# Sheet1.net
KiCad netlist of a schematic drawn in Altium Designer
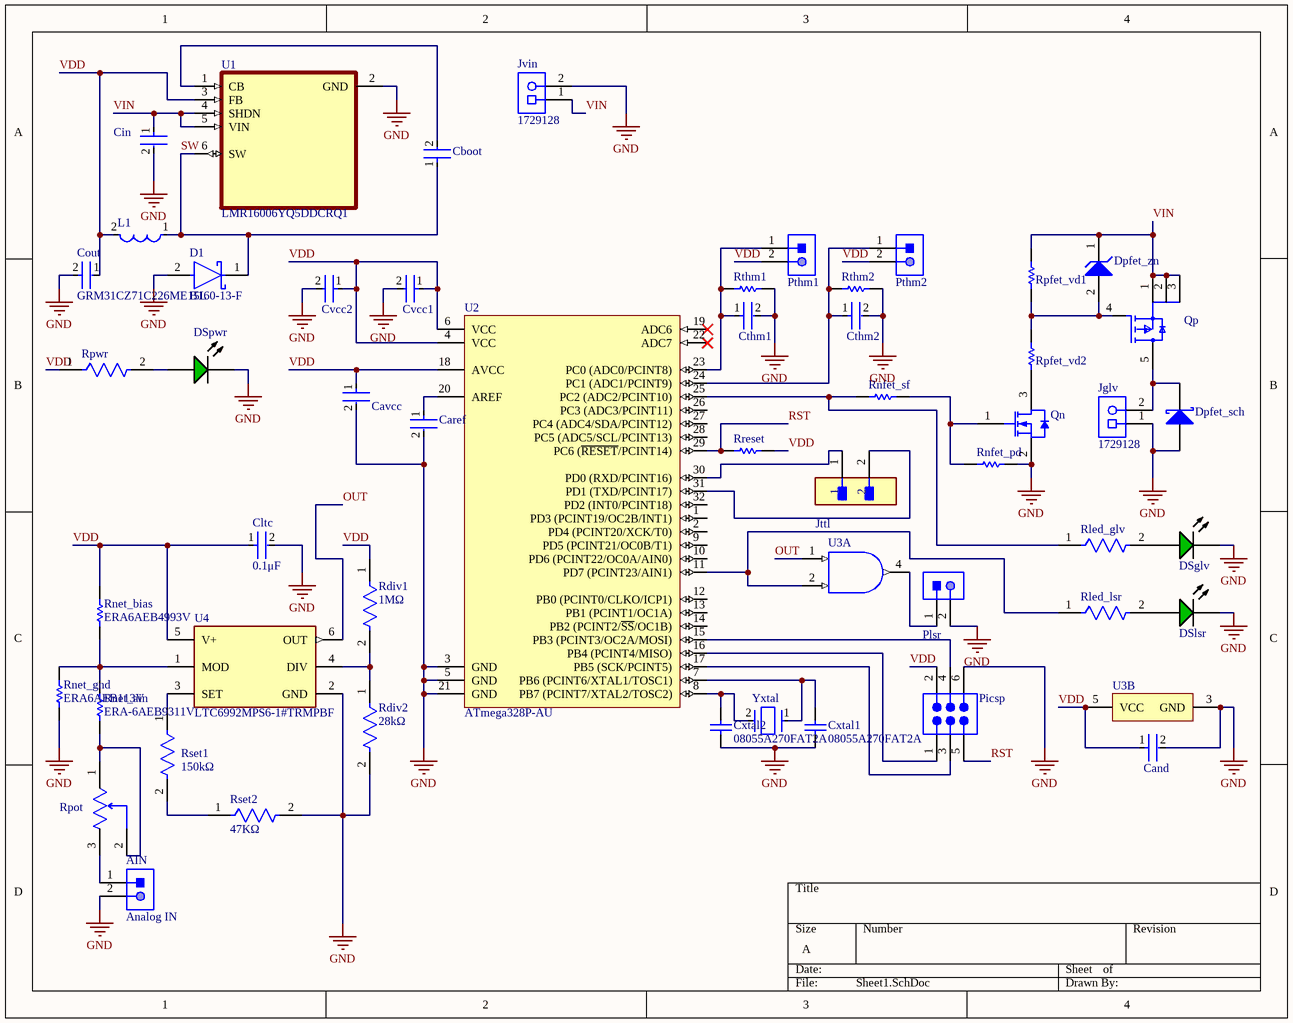
[diagram p0: Sheet1.SchDoc]

(export (version "E")
  (design (tool "Eeschema 10.0.6"))
  (components
    (comp (ref "AIN")
      (value "Analog IN")
      (footprint "JST-S2B-XH-A(LF)(SN)_V")
      (fields (field (name "TOLERANCE") "10%"))
      (libsource (lib "") (part "CN-1P-M-R2_1"))
    )
    (comp (ref "Cand")
      (value "GCM21BR72A104KA37L")
      (footprint "FP-GCM21B-0_15-MFG")
      (description "Ceramic Capacitor for Automotive 100nF ±10% 100VDC X7R 0805 Embossed T/R")
      (fields (field (name "TOLERANCE") "10%") (field (name "VOLTAGE") "100V"))
      (libsource (lib "Altium Content Vault") (part "02cd4be3c70576c341d710602a673aa"))
    )
    (comp (ref "Caref")
      (value "GCM21BR72A104KA37L")
      (footprint "FP-GCM21B-0_15-MFG")
      (description "Ceramic Capacitor for Automotive 100nF ±10% 100VDC X7R 0805 Embossed T/R")
      (fields (field (name "TOLERANCE") "10%") (field (name "VOLTAGE") "100V"))
      (libsource (lib "Altium Content Vault") (part "02cd4be3c70576c341d710602a673aa"))
    )
    (comp (ref "Cavcc")
      (value "GCM21BR72A104KA37L")
      (footprint "FP-GCM21B-0_15-MFG")
      (description "Ceramic Capacitor for Automotive 100nF ±10% 100VDC X7R 0805 Embossed T/R")
      (fields (field (name "TOLERANCE") "10%") (field (name "VOLTAGE") "100V"))
      (libsource (lib "Altium Content Vault") (part "02cd4be3c70576c341d710602a673aa"))
    )
    (comp (ref "Cboot")
      (value "GRM21BR71H474KA88L")
      (footprint "FP-GRM21B-0_1-IPC_B")
      (description "Chip Multilayer Ceramic Capacitors for General Purpose, 0805, 0.47uF, X7R, 15%, 10%, 50V")
      (fields (field (name "VOLTAGE") "50V") (field (name "TOLERANCE") "10%"))
      (libsource (lib "Altium Content Vault") (part "b4654b650e69147ec39a6b967a45e02"))
    )
    (comp (ref "Cin")
      (value "GRM31CR71H475KA12L")
      (footprint "FP-GRM31C-0_2-e0_3_0_8-IPC_C")
      (description "Chip Multilayer Ceramic Capacitors for General Purpose, 1206, 4.7uF, X7R, 15%, 10%, 50V")
      (fields (field (name "VOLTAGE") "50V") (field (name "TOLERANCE") "10%"))
      (libsource (lib "Altium Content Vault") (part "02cd4be3c70576c341d710602a673aa"))
    )
    (comp (ref "Cltc")
      (value "0.1μF")
      (footprint "FP-GCM21B-0_15-MFG")
      (description "Ceramic Capacitor for Automotive 100nF ±10% 100VDC X7R 0805 Embossed T/R")
      (fields (field (name "TOLERANCE") "10%") (field (name "VOLTAGE") "100V"))
      (libsource (lib "Altium Content Vault") (part "02cd4be3c70576c341d710602a673aa"))
    )
    (comp (ref "Cout")
      (value "GRM31CZ71C226ME15L")
      (footprint "FP-GRM31C-0_3-e0_3_0_8-IPC_C")
      (description "Chip Multilayer Ceramic Capacitors for General Purpose, 1206, 22uF, X7R, 15%, 20%, 16V")
      (libsource (lib "Altium Content Vault") (part "f23184f103b6ebe33a8c269c53dcba6"))
    )
    (comp (ref "Cthm1")
      (value "GCM21BR72A104KA37L")
      (footprint "FP-GCM21B-0_15-MFG")
      (description "Ceramic Capacitor for Automotive 100nF ±10% 100VDC X7R 0805 Embossed T/R")
      (fields (field (name "TOLERANCE") "10%") (field (name "VOLTAGE") "100V"))
      (libsource (lib "Altium Content Vault") (part "02cd4be3c70576c341d710602a673aa"))
    )
    (comp (ref "Cthm2")
      (value "GCM21BR72A104KA37L")
      (footprint "FP-GCM21B-0_15-MFG")
      (description "Ceramic Capacitor for Automotive 100nF ±10% 100VDC X7R 0805 Embossed T/R")
      (fields (field (name "TOLERANCE") "10%") (field (name "VOLTAGE") "100V"))
      (libsource (lib "Altium Content Vault") (part "02cd4be3c70576c341d710602a673aa"))
    )
    (comp (ref "Cvcc1")
      (value "GCM21BR72A104KA37L")
      (footprint "FP-GCM21B-0_15-MFG")
      (description "Ceramic Capacitor for Automotive 100nF ±10% 100VDC X7R 0805 Embossed T/R")
      (fields (field (name "TOLERANCE") "10%") (field (name "VOLTAGE") "100V"))
      (libsource (lib "Altium Content Vault") (part "02cd4be3c70576c341d710602a673aa"))
    )
    (comp (ref "Cvcc2")
      (value "GCM21BR72A104KA37L")
      (footprint "FP-GCM21B-0_15-MFG")
      (description "Ceramic Capacitor for Automotive 100nF ±10% 100VDC X7R 0805 Embossed T/R")
      (fields (field (name "TOLERANCE") "10%") (field (name "VOLTAGE") "100V"))
      (libsource (lib "Altium Content Vault") (part "02cd4be3c70576c341d710602a673aa"))
    )
    (comp (ref "Cxtal1")
      (value "08055A270FAT2A")
      (footprint "CAPC2013X94X50NL20T25")
      (fields (field (name "MANUFACTURER") "AVX Interconnect / Elco"))
      (libsource (lib "Altium Content Vault") (part "CAP"))
    )
    (comp (ref "Cxtal2")
      (value "08055A270FAT2A")
      (footprint "CAPC2013X94X50NL20T25")
      (fields (field (name "MANUFACTURER") "AVX Interconnect / Elco"))
      (libsource (lib "Altium Content Vault") (part "CAP"))
    )
    (comp (ref "D1")
      (value "B160-13-F")
      (footprint "FP-SMA-MFG")
      (description "DIODE SCHOTTKY 60V 1A SMA")
      (libsource (lib "Altium Content Vault") (part "1d6ec82d83fb6aee721767c19dac4b9"))
    )
    (comp (ref "Dpfet_sch")
      (value "B560C-13-F")
      (footprint "DIOD-B5X0C-2_M")
      (description "Schottky Barrier Rectifier, 5 A, 60 V, -55 to 125 degC, 2-Pin SMD, RoHS, Tape and Reel")
      (fields (field (name "MANUFACTURER") "DiodesIncorporated"))
      (libsource (lib "Altium Content Vault") (part "DSKY-KA-2"))
    )
    (comp (ref "Dpfet_zn")
      (value "MMSZ5245BT1G")
      (footprint "ONSC-SOD-123-2-425-04_V")
      (description "Zener Voltage Regulator, 500 mW, 2-Pin SOD-123, Pb-Free, Tape and Reel")
      (fields (field (name "MANUFACTURER") "On Semiconductor"))
      (libsource (lib "Altium Content Vault") (part "ONSC-K1A2-2"))
    )
    (comp (ref "DSglv")
      (value "HSMG-C170")
      (footprint "AVAG-HSMX-C170_V")
      (description "Chip LED, Green, 2.2 V, -40 to 85 degC, 2-Pin SMD, Pb-Free, Tape and Reel")
      (fields (field (name "MANUFACTURER") "Avago"))
      (libsource (lib "Altium Content Vault") (part "LED_GREEN_A1K2-2"))
    )
    (comp (ref "DSlsr")
      (value "HSMG-C170")
      (footprint "AVAG-HSMX-C170_V")
      (description "Chip LED, Green, 2.2 V, -40 to 85 degC, 2-Pin SMD, Pb-Free, Tape and Reel")
      (fields (field (name "MANUFACTURER") "Avago"))
      (libsource (lib "Altium Content Vault") (part "LED_GREEN_A1K2-2"))
    )
    (comp (ref "DSpwr")
      (value "HSMG-C170")
      (footprint "AVAG-HSMX-C170_V")
      (description "Chip LED, Green, 2.2 V, -40 to 85 degC, 2-Pin SMD, Pb-Free, Tape and Reel")
      (fields (field (name "MANUFACTURER") "Avago"))
      (libsource (lib "Altium Content Vault") (part "LED_GREEN_A1K2-2"))
    )
    (comp (ref "Jglv")
      (value "1729128")
      (footprint "PHOE-1729128-2_V")
      (description "PCB Terminal Block, 13.5 A, 400 V, 2-Pin THD, RoHS, Bulk")
      (fields (field (name "MANUFACTURER") "Phoenix Contact"))
      (libsource (lib "Altium Content Vault") (part "CN-2P-F-R2"))
    )
    (comp (ref "Jttl")
      (value "TSW-102-07-F-S")
      (footprint "FP-TSW-102-07-F-S-MFG")
      (description "CONN HEADER VERT 2POS 2.54MM")
      (libsource (lib "Altium Content Vault") (part "3bc925449376181038e59eaffc5286c"))
    )
    (comp (ref "Jvin")
      (value "1729128")
      (footprint "PHOE-1729128-2_V")
      (description "PCB Terminal Block, 13.5 A, 400 V, 2-Pin THD, RoHS, Bulk")
      (fields (field (name "MANUFACTURER") "Phoenix Contact"))
      (libsource (lib "Altium Content Vault") (part "CN-2P-F-R2"))
    )
    (comp (ref "L1")
      (value "LQH5BPN100MT0L")
      (footprint "FP-LQH5BPB_T0-MFG")
      (description "Wire Wound Ferrite Inductor for Power Lines 10μH ±20% 0.1272Ω 1.60A 2020")
      (fields (field (name "TOLERANCE") "20%"))
      (libsource (lib "Altium Content Vault") (part "725321dda6339637d4d059423bc1c3c"))
    )
    (comp (ref "Picsp")
      (value "MTSW-103-07-F-D-244")
      (footprint "SMTC-MTSW-103-07-X-D-244")
      (fields (field (name "MANUFACTURER") "Samtec"))
      (libsource (lib "Altium Content Vault") (part "SMTC-MTSW-103-07-X-D-244"))
    )
    (comp (ref "Plsr")
      (value "S2B-XH-A(LF)(SN)")
      (footprint "JST-S2B-XH-A(LF)(SN)_V")
      (fields (field (name "TOLERANCE") "10%"))
      (libsource (lib "Altium Content Vault") (part "CN-1P-M-R2"))
    )
    (comp (ref "Pthm1")
      (value "S2B-XH-A(LF)(SN)")
      (footprint "JST-S2B-XH-A(LF)(SN)_V")
      (fields (field (name "TOLERANCE") "10%"))
      (libsource (lib "") (part "CN-1P-M-R2_1"))
    )
    (comp (ref "Pthm2")
      (value "S2B-XH-A(LF)(SN)")
      (footprint "JST-S2B-XH-A(LF)(SN)_V")
      (fields (field (name "TOLERANCE") "10%"))
      (libsource (lib "") (part "CN-1P-M-R2_1"))
    )
    (comp (ref "Qn")
      (value "2N7002LT1G")
      (footprint "ONSC-SOT-23-3-318-08_V")
      (description "Small Signal MOSFET, 60 V, 115 mA, N-Channel, 3-Pin SOT-23, Pb-Free, Tape and Reel")
      (fields (field (name "MANUFACTURER") "On Semiconductor"))
      (libsource (lib "Altium Content Vault") (part "ONSC-NMOS-G1S2D3-3"))
    )
    (comp (ref "Qp")
      (value "SQJ459EP-T1_GE3")
      (footprint "FP-C15-1203-SINGLE-MFG")
      (description "MOSFET P-CH 60V 52A POWERPAKSO-8")
      (fields
        (field (name "MANUFACTURER") "Vishay")
        (field (name "OCTOPART") "https://octopart.com/sqj459ep-t1_ge3-vishay-73080141")
      )
      (libsource (lib "Altium Content Vault") (part "5cd5aa5b3d227f8a38aca373915d141"))
    )
    (comp (ref "Rdiv1")
      (value "1MΩ")
      (footprint "FP-RG2012-MFG")
      (description "Automotive Metal Thin Film Chip Resistor, 0805, 1MΩ, 0.1%, 25ppm/°C, 0.125W, 150V")
      (fields (field (name "TOLERANCE") "0.1%"))
      (libsource (lib "Altium Content Vault") (part "1029c3af85768c4190bb7ad29bc67b5"))
    )
    (comp (ref "Rdiv2")
      (value "28kΩ")
      (footprint "FP-RG2012-MFG")
      (description "Automotive Metal Thin Film Chip Resistor, 0805, 280kΩ, 0.1%, 25ppm/°C, 0.125W, 150V")
      (fields (field (name "TOLERANCE") "0.1%"))
      (libsource (lib "Altium Content Vault") (part "1029c3af85768c4190bb7ad29bc67b5"))
    )
    (comp (ref "Rled_glv")
      (value "CRCW08051K20FKEA")
      (footprint "FP-CRCW0805-e3-MFG")
      (description "RES Thick Film, 1.2kΩ, 1%, 0.125W, 100ppm/°C, 0805")
      (fields (field (name "TOLERANCE") "1%"))
      (libsource (lib "Altium Content Vault") (part "1029c3af85768c4190bb7ad29bc67b5"))
    )
    (comp (ref "Rled_lsr")
      (value "CRCW08051K20FKEA")
      (footprint "FP-CRCW0805-e3-MFG")
      (description "RES Thick Film, 1.2kΩ, 1%, 0.125W, 100ppm/°C, 0805")
      (fields (field (name "TOLERANCE") "1%"))
      (libsource (lib "Altium Content Vault") (part "1029c3af85768c4190bb7ad29bc67b5"))
    )
    (comp (ref "Rnet_ain")
      (value "ERA-6AEB9311V")
      (footprint "RESC2013X60X40ML20T25")
      (fields (field (name "PART NUMBER") "ERA6AEB472V") (field (name "MANUFACTURER") "Panasonic"))
      (libsource (lib "Altium Content Vault") (part "RES"))
    )
    (comp (ref "Rnet_bias")
      (value "ERA6AEB4993V")
      (footprint "RESC2013X60X40ML20T25")
      (fields (field (name "MANUFACTURER") "Panasonic"))
      (libsource (lib "Altium Content Vault") (part "RES"))
    )
    (comp (ref "Rnet_gnd")
      (value "ERA6AEB113V")
      (footprint "RESC2013X60X40NL20T25")
      (fields (field (name "MANUFACTURER") "Panasonic"))
      (libsource (lib "Altium Content Vault") (part "RES"))
    )
    (comp (ref "Rnfet_pd")
      (value "ERA-6AEB103V")
      (footprint "RESC2013X60X40LL20T25_A")
      (fields (field (name "TOLERANCE") "0.1%") (field (name "MANUFACTURER") "Panasonic"))
      (libsource (lib "Altium Content Vault") (part "RES-2"))
    )
    (comp (ref "Rnfet_sf")
      (value "ERA6AEB331V")
      (footprint "RESC2013X60X40LL20T25")
      (fields (field (name "MANUFACTURER") "Panasonic"))
      (libsource (lib "Altium Content Vault") (part "RES"))
    )
    (comp (ref "Rpfet_vd1")
      (value "ERA-6AEB103V")
      (footprint "RESC2013X60X40LL20T25_A")
      (fields (field (name "TOLERANCE") "0.1%") (field (name "MANUFACTURER") "Panasonic"))
      (libsource (lib "Altium Content Vault") (part "RES-2"))
    )
    (comp (ref "Rpfet_vd2")
      (value "ERA-6AEB103V")
      (footprint "RESC2013X60X40LL20T25_A")
      (fields (field (name "TOLERANCE") "0.1%") (field (name "MANUFACTURER") "Panasonic"))
      (libsource (lib "Altium Content Vault") (part "RES-2"))
    )
    (comp (ref "Rpot")
      (value "3296W-1-202LF")
      (footprint "FP-3296W-MFG")
      (description "TRIMMER 2K OHM 0.5W PC PIN TOP")
      (fields (field (name "TOLERANCE") "10%"))
      (libsource (lib "Altium Content Vault") (part "81a8d1f2e6c155a1fa928b358d1a42a"))
    )
    (comp (ref "Rpwr")
      (value "CRCW08051K20FKEA")
      (footprint "FP-CRCW0805-e3-MFG")
      (description "RES Thick Film, 1.2kΩ, 1%, 0.125W, 100ppm/°C, 0805")
      (fields (field (name "TOLERANCE") "1%"))
      (libsource (lib "Altium Content Vault") (part "1029c3af85768c4190bb7ad29bc67b5"))
    )
    (comp (ref "Rreset")
      (value "ERA-6AEB103V")
      (footprint "RESC2013X60X40LL20T25_A")
      (fields (field (name "TOLERANCE") "0.1%") (field (name "MANUFACTURER") "Panasonic"))
      (libsource (lib "Altium Content Vault") (part "RES-2"))
    )
    (comp (ref "Rset1")
      (value "150kΩ")
      (footprint "FP-ERA6A-MFG")
      (description "RES 150K OHM 0.1% 1/8W 0805")
      (fields (field (name "TOLERANCE") "0.1%"))
      (libsource (lib "Altium Content Vault") (part "1029c3af85768c4190bb7ad29bc67b5"))
    )
    (comp (ref "Rset2")
      (value "47KΩ")
      (footprint "FP-ERA6A-MFG")
      (fields (field (name "TOLERANCE") "0.1%"))
      (libsource (lib "Altium Content Vault") (part "1029c3af85768c4190bb7ad29bc67b5"))
    )
    (comp (ref "Rthm1")
      (value "ERA-6AEB103V")
      (footprint "RESC2013X60X40LL20T25_A")
      (fields (field (name "TOLERANCE") "0.1%") (field (name "MANUFACTURER") "Panasonic"))
      (libsource (lib "Altium Content Vault") (part "RES-2"))
    )
    (comp (ref "Rthm2")
      (value "ERA-6AEB103V")
      (footprint "RESC2013X60X40LL20T25_A")
      (fields (field (name "TOLERANCE") "0.1%") (field (name "MANUFACTURER") "Panasonic"))
      (libsource (lib "Altium Content Vault") (part "RES-2"))
    )
    (comp (ref "U1")
      (value "LMR16006YQ5DDCRQ1")
      (footprint "SOT95P280X110-6N")
      (description "Automotive Qualified SIMPLE SWITCHER庐 40V (65V transient), 0.6A Buck Regulator with 28渭A IQ")
      (fields (field (name "MF") "Texas Instruments"))
      (libsource (lib "LMR16006YQ5DDCRQ1") (part "LMR16006YQ5DDCRQ1"))
    )
    (comp (ref "U2")
      (value "ATmega328P-AU")
      (footprint "32A_M")
      (libsource (lib "Altium Content Vault") (part "MC-8B-ATM48-SQ32"))
    )
    (comp (ref "U3")
      (value "SN74LVC1G08DBVR")
      (footprint "DBV0005A_M")
      (description "Single 2-Input Positive-AND Gate, DBV0005A, LARGE T&R")
      (fields
        (field (name "GENERIC PART NUMBER") "SN74LVC1G08")
        (field (name "MANUFACTURER") "Texas Instruments")
      )
      (libsource (lib "Altium Content Vault") (part "TI-SN74XXX1X08-5"))
    )
    (comp (ref "U4")
      (value "LTC6992MPS6-1#TRMPBF")
      (footprint "FP-S6-6-05-08-1636-IPC_B")
      (description "IC OSC SILICON PROG TSOT23-6")
      (libsource (lib "Altium Content Vault") (part "8a48498f8010dc692cf6b2ba4f9d0e7"))
    )
    (comp (ref "Yxtal")
      (value "ABLS-16.000MHZ-K4T")
      (footprint "FP-ABLS-MFG")
      (description "CRYSTAL 16.0000MHZ 18PF SMD")
      (fields
        (field (name "TOLERANCE") "30ppm")
        (field (name "OCTOPART") "https://octopart.com/abls-16.000mhz-k4t-abracon-18618626")
      )
      (libsource (lib "Altium Content Vault") (part "c23a69dc6c9e2f18f2079038eb95dd1"))
    )
  )
  (nets
    (net (code "1") (name "/OUT") (class "Default")
      (node (ref "U3") (pin "1") (pinfunction "A_1") (pintype "input"))
      (node (ref "U4") (pin "6") (pinfunction "OUT_6") (pintype "output"))
    )
    (net (code "2") (name "/RST") (class "Default")
      (node (ref "Picsp") (pin "5") (pinfunction "5_5") (pintype "passive"))
      (node (ref "Rreset") (pin "1") (pinfunction "1_1") (pintype "passive"))
      (node (ref "U2") (pin "29") (pinfunction "PC6_(~{RESET}/PCINT14)_29") (pintype "bidirectional"))
    )
    (net (code "3") (name "/SW") (class "Default")
      (node (ref "Cboot") (pin "1") (pinfunction "1_1") (pintype "passive"))
      (node (ref "D1") (pin "1") (pinfunction "C_1") (pintype "passive"))
      (node (ref "L1") (pin "1") (pinfunction "1_1") (pintype "passive"))
      (node (ref "U1") (pin "6") (pinfunction "SW_6") (pintype "bidirectional"))
    )
    (net (code "4") (name "/VDD") (class "Default")
      (node (ref "Cand") (pin "1") (pinfunction "1_1") (pintype "passive"))
      (node (ref "Cavcc") (pin "1") (pinfunction "1_1") (pintype "passive"))
      (node (ref "Cltc") (pin "1") (pinfunction "1_1") (pintype "passive"))
      (node (ref "Cout") (pin "1") (pinfunction "1_1") (pintype "passive"))
      (node (ref "Cvcc1") (pin "1") (pinfunction "1_1") (pintype "passive"))
      (node (ref "Cvcc2") (pin "1") (pinfunction "1_1") (pintype "passive"))
      (node (ref "L1") (pin "2") (pinfunction "2_2") (pintype "passive"))
      (node (ref "Picsp") (pin "2") (pinfunction "2_2") (pintype "passive"))
      (node (ref "Pthm1") (pin "2") (pinfunction "2_2") (pintype "passive"))
      (node (ref "Pthm2") (pin "2") (pinfunction "2_2") (pintype "passive"))
      (node (ref "Rdiv1") (pin "1") (pinfunction "1_1") (pintype "passive"))
      (node (ref "Rnet_bias") (pin "2") (pinfunction "2_2") (pintype "passive"))
      (node (ref "Rpwr") (pin "1") (pinfunction "1_1") (pintype "passive"))
      (node (ref "Rreset") (pin "2") (pinfunction "2_2") (pintype "passive"))
      (node (ref "U1") (pin "3") (pinfunction "FB_3") (pintype "input"))
      (node (ref "U2") (pin "18") (pinfunction "AVCC_18") (pintype "power_in"))
      (node (ref "U2") (pin "4") (pinfunction "VCC_4") (pintype "power_in"))
      (node (ref "U2") (pin "6") (pinfunction "VCC_6") (pintype "power_in"))
      (node (ref "U3") (pin "5") (pinfunction "VCC_5") (pintype "power_in"))
      (node (ref "U4") (pin "5") (pinfunction "V+_5") (pintype "power_in"))
    )
    (net (code "5") (name "/VIN") (class "Default")
      (node (ref "Cin") (pin "1") (pinfunction "1_1") (pintype "passive"))
      (node (ref "Dpfet_zn") (pin "1") (pinfunction "K_1") (pintype "passive"))
      (node (ref "Jvin") (pin "1") (pinfunction "1_1") (pintype "passive"))
      (node (ref "Qp") (pin "1") (pinfunction "S_1") (pintype "passive"))
      (node (ref "Qp") (pin "2") (pinfunction "S_2") (pintype "passive"))
      (node (ref "Qp") (pin "3") (pinfunction "S_3") (pintype "passive"))
      (node (ref "Rpfet_vd1") (pin "2") (pinfunction "2_2") (pintype "passive"))
      (node (ref "U1") (pin "4") (pinfunction "SHDN_4") (pintype "input"))
      (node (ref "U1") (pin "5") (pinfunction "VIN_5") (pintype "input"))
    )
    (net (code "6") (name "GND") (class "Default")
      (node (ref "AIN") (pin "2") (pinfunction "2_2") (pintype "passive"))
      (node (ref "Cand") (pin "2") (pinfunction "2_2") (pintype "passive"))
      (node (ref "Caref") (pin "2") (pinfunction "2_2") (pintype "passive"))
      (node (ref "Cavcc") (pin "2") (pinfunction "2_2") (pintype "passive"))
      (node (ref "Cin") (pin "2") (pinfunction "2_2") (pintype "passive"))
      (node (ref "Cltc") (pin "2") (pinfunction "2_2") (pintype "passive"))
      (node (ref "Cout") (pin "2") (pinfunction "2_2") (pintype "passive"))
      (node (ref "Cthm1") (pin "2") (pinfunction "2_2") (pintype "passive"))
      (node (ref "Cthm2") (pin "2") (pinfunction "2_2") (pintype "passive"))
      (node (ref "Cvcc1") (pin "2") (pinfunction "2_2") (pintype "passive"))
      (node (ref "Cvcc2") (pin "2") (pinfunction "2_2") (pintype "passive"))
      (node (ref "Cxtal1") (pin "1") (pinfunction "1_1") (pintype "passive"))
      (node (ref "Cxtal2") (pin "1") (pinfunction "1_1") (pintype "passive"))
      (node (ref "D1") (pin "2") (pinfunction "A_2") (pintype "passive"))
      (node (ref "DSglv") (pin "2") (pinfunction "K_2") (pintype "passive"))
      (node (ref "DSlsr") (pin "2") (pinfunction "K_2") (pintype "passive"))
      (node (ref "DSpwr") (pin "2") (pinfunction "K_2") (pintype "passive"))
      (node (ref "Dpfet_sch") (pin "2") (pinfunction "A_2") (pintype "passive"))
      (node (ref "Jglv") (pin "1") (pinfunction "1_1") (pintype "passive"))
      (node (ref "Jvin") (pin "2") (pinfunction "2_2") (pintype "passive"))
      (node (ref "Picsp") (pin "6") (pinfunction "6_6") (pintype "passive"))
      (node (ref "Plsr") (pin "2") (pinfunction "2_2") (pintype "passive"))
      (node (ref "Qn") (pin "2") (pinfunction "S_2") (pintype "passive"))
      (node (ref "Rdiv2") (pin "2") (pinfunction "2_2") (pintype "passive"))
      (node (ref "Rnet_gnd") (pin "1") (pinfunction "1_1") (pintype "passive"))
      (node (ref "Rnfet_pd") (pin "2") (pinfunction "2_2") (pintype "passive"))
      (node (ref "Rset2") (pin "2") (pinfunction "2_2") (pintype "passive"))
      (node (ref "Rthm1") (pin "2") (pinfunction "2_2") (pintype "passive"))
      (node (ref "Rthm2") (pin "2") (pinfunction "2_2") (pintype "passive"))
      (node (ref "U1") (pin "2") (pinfunction "GND_2") (pintype "power_in"))
      (node (ref "U2") (pin "21") (pinfunction "GND_21") (pintype "power_in"))
      (node (ref "U2") (pin "3") (pinfunction "GND_3") (pintype "power_in"))
      (node (ref "U2") (pin "5") (pinfunction "GND_5") (pintype "power_in"))
      (node (ref "U3") (pin "3") (pinfunction "GND_3") (pintype "power_in"))
      (node (ref "U4") (pin "2") (pinfunction "GND_2") (pintype "power_in"))
    )
    (net (code "7") (name "Net-(DSglv-A)") (class "Default")
      (node (ref "DSglv") (pin "1") (pinfunction "A_1") (pintype "passive"))
      (node (ref "Rled_glv") (pin "2") (pinfunction "2_2") (pintype "passive"))
    )
    (net (code "8") (name "Net-(DSlsr-A)") (class "Default")
      (node (ref "DSlsr") (pin "1") (pinfunction "A_1") (pintype "passive"))
      (node (ref "Rled_lsr") (pin "2") (pinfunction "2_2") (pintype "passive"))
    )
    (net (code "9") (name "Net-(DSpwr-A)") (class "Default")
      (node (ref "DSpwr") (pin "1") (pinfunction "A_1") (pintype "passive"))
      (node (ref "Rpwr") (pin "2") (pinfunction "2_2") (pintype "passive"))
    )
    (net (code "10") (name "Net-(Dpfet_sch-K)") (class "Default")
      (node (ref "Dpfet_sch") (pin "1") (pinfunction "K_1") (pintype "passive"))
      (node (ref "Jglv") (pin "2") (pinfunction "2_2") (pintype "passive"))
      (node (ref "Qp") (pin "5") (pinfunction "D_5") (pintype "passive"))
    )
    (net (code "11") (name "Net-(Dpfet_zn-A)") (class "Default")
      (node (ref "Dpfet_zn") (pin "2") (pinfunction "A_2") (pintype "passive"))
      (node (ref "Qp") (pin "4") (pinfunction "G_4") (pintype "passive"))
      (node (ref "Rpfet_vd1") (pin "1") (pinfunction "1_1") (pintype "passive"))
      (node (ref "Rpfet_vd2") (pin "1") (pinfunction "1_1") (pintype "passive"))
    )
    (net (code "12") (name "Net-(Qn-D)") (class "Default")
      (node (ref "Qn") (pin "3") (pinfunction "D_3") (pintype "passive"))
      (node (ref "Rpfet_vd2") (pin "2") (pinfunction "2_2") (pintype "passive"))
    )
    (net (code "13") (name "Net-(Qn-G)") (class "Default")
      (node (ref "Qn") (pin "1") (pinfunction "G_1") (pintype "passive"))
      (node (ref "Rnfet_pd") (pin "1") (pinfunction "1_1") (pintype "passive"))
      (node (ref "Rnfet_sf") (pin "2") (pinfunction "2_2") (pintype "passive"))
    )
    (net (code "14") (name "Net-(Rpot-CCW)") (class "Default")
      (node (ref "Rnet_ain") (pin "1") (pinfunction "1_1") (pintype "passive"))
      (node (ref "Rpot") (pin "1") (pinfunction "CCW_1") (pintype "passive"))
      (node (ref "Rpot") (pin "2") (pinfunction "WIPER_2") (pintype "passive"))
    )
    (net (code "15") (name "Net-(Rpot-CW)") (class "Default")
      (node (ref "AIN") (pin "1") (pinfunction "1_1") (pintype "passive"))
      (node (ref "Rpot") (pin "3") (pinfunction "CW_3") (pintype "passive"))
    )
    (net (code "16") (name "Net-(Rset1-Pad2)") (class "Default")
      (node (ref "Rset1") (pin "2") (pinfunction "2_2") (pintype "passive"))
      (node (ref "Rset2") (pin "1") (pinfunction "1_1") (pintype "passive"))
    )
    (net (code "17") (name "Net-(U1-CB)") (class "Default")
      (node (ref "Cboot") (pin "2") (pinfunction "2_2") (pintype "passive"))
      (node (ref "U1") (pin "1") (pinfunction "CB_1") (pintype "input"))
    )
    (net (code "18") (name "Net-(U2-AREF)") (class "Default")
      (node (ref "Caref") (pin "1") (pinfunction "1_1") (pintype "passive"))
      (node (ref "U2") (pin "20") (pinfunction "AREF_20") (pintype "passive"))
    )
    (net (code "19") (name "Net-(U2-PB3_(PCINT3{slash}OC2A{slash}MOSI))") (class "Default")
      (node (ref "Picsp") (pin "4") (pinfunction "4_4") (pintype "passive"))
      (node (ref "U2") (pin "15") (pinfunction "PB3_(PCINT3/OC2A/MOSI)_15") (pintype "bidirectional"))
    )
    (net (code "20") (name "Net-(U2-PB4_(PCINT4{slash}MISO))") (class "Default")
      (node (ref "Picsp") (pin "1") (pinfunction "1_1") (pintype "passive"))
      (node (ref "U2") (pin "16") (pinfunction "PB4_(PCINT4/MISO)_16") (pintype "bidirectional"))
    )
    (net (code "21") (name "Net-(U2-PB5_(SCK{slash}PCINT5))") (class "Default")
      (node (ref "Picsp") (pin "3") (pinfunction "3_3") (pintype "passive"))
      (node (ref "U2") (pin "17") (pinfunction "PB5_(SCK/PCINT5)_17") (pintype "bidirectional"))
    )
    (net (code "22") (name "Net-(U2-PB6_(PCINT6{slash}XTAL1{slash}TOSC1))") (class "Default")
      (node (ref "Cxtal1") (pin "2") (pinfunction "2_2") (pintype "passive"))
      (node (ref "U2") (pin "7") (pinfunction "PB6_(PCINT6/XTAL1/TOSC1)_7") (pintype "bidirectional"))
      (node (ref "Yxtal") (pin "1") (pinfunction "1_1") (pintype "passive"))
    )
    (net (code "23") (name "Net-(U2-PB7_(PCINT7{slash}XTAL2{slash}TOSC2))") (class "Default")
      (node (ref "Cxtal2") (pin "2") (pinfunction "2_2") (pintype "passive"))
      (node (ref "U2") (pin "8") (pinfunction "PB7_(PCINT7/XTAL2/TOSC2)_8") (pintype "bidirectional"))
      (node (ref "Yxtal") (pin "2") (pinfunction "2_2") (pintype "passive"))
    )
    (net (code "24") (name "Net-(U2-PC0_(ADC0{slash}PCINT8))") (class "Default")
      (node (ref "Cthm1") (pin "1") (pinfunction "1_1") (pintype "passive"))
      (node (ref "Pthm1") (pin "1") (pinfunction "1_1") (pintype "passive"))
      (node (ref "Rthm1") (pin "1") (pinfunction "1_1") (pintype "passive"))
      (node (ref "U2") (pin "23") (pinfunction "PC0_(ADC0/PCINT8)_23") (pintype "bidirectional"))
    )
    (net (code "25") (name "Net-(U2-PC1_(ADC1{slash}PCINT9))") (class "Default")
      (node (ref "Cthm2") (pin "1") (pinfunction "1_1") (pintype "passive"))
      (node (ref "Pthm2") (pin "1") (pinfunction "1_1") (pintype "passive"))
      (node (ref "Rthm2") (pin "1") (pinfunction "1_1") (pintype "passive"))
      (node (ref "U2") (pin "24") (pinfunction "PC1_(ADC1/PCINT9)_24") (pintype "bidirectional"))
    )
    (net (code "26") (name "Net-(U2-PC2_(ADC2{slash}PCINT10))") (class "Default")
      (node (ref "Rled_glv") (pin "1") (pinfunction "1_1") (pintype "passive"))
      (node (ref "Rnfet_sf") (pin "1") (pinfunction "1_1") (pintype "passive"))
      (node (ref "U2") (pin "25") (pinfunction "PC2_(ADC2/PCINT10)_25") (pintype "bidirectional"))
    )
    (net (code "27") (name "Net-(U2-PD0_(RXD{slash}PCINT16))") (class "Default")
      (node (ref "Jttl") (pin "1") (pinfunction "1_1") (pintype "passive"))
      (node (ref "U2") (pin "30") (pinfunction "PD0_(RXD/PCINT16)_30") (pintype "bidirectional"))
    )
    (net (code "28") (name "Net-(U2-PD1_(TXD{slash}PCINT17))") (class "Default")
      (node (ref "Jttl") (pin "2") (pinfunction "2_2") (pintype "passive"))
      (node (ref "U2") (pin "31") (pinfunction "PD1_(TXD/PCINT17)_31") (pintype "bidirectional"))
    )
    (net (code "29") (name "Net-(U2-PD7_(PCINT23{slash}AIN1))") (class "Default")
      (node (ref "Rled_lsr") (pin "1") (pinfunction "1_1") (pintype "passive"))
      (node (ref "U2") (pin "11") (pinfunction "PD7_(PCINT23/AIN1)_11") (pintype "bidirectional"))
      (node (ref "U3") (pin "2") (pinfunction "B_2") (pintype "input"))
    )
    (net (code "30") (name "Net-(U3A-Y)") (class "Default")
      (node (ref "Plsr") (pin "1") (pinfunction "1_1") (pintype "passive"))
      (node (ref "U3") (pin "4") (pinfunction "Y_4") (pintype "output"))
    )
    (net (code "31") (name "Net-(U4-DIV)") (class "Default")
      (node (ref "Rdiv1") (pin "2") (pinfunction "2_2") (pintype "passive"))
      (node (ref "Rdiv2") (pin "1") (pinfunction "1_1") (pintype "passive"))
      (node (ref "U4") (pin "4") (pinfunction "DIV_4") (pintype "passive"))
    )
    (net (code "32") (name "Net-(U4-MOD)") (class "Default")
      (node (ref "Rnet_ain") (pin "2") (pinfunction "2_2") (pintype "passive"))
      (node (ref "Rnet_bias") (pin "1") (pinfunction "1_1") (pintype "passive"))
      (node (ref "Rnet_gnd") (pin "2") (pinfunction "2_2") (pintype "passive"))
      (node (ref "U4") (pin "1") (pinfunction "MOD_1") (pintype "passive"))
    )
    (net (code "33") (name "Net-(U4-SET)") (class "Default")
      (node (ref "Rset1") (pin "1") (pinfunction "1_1") (pintype "passive"))
      (node (ref "U4") (pin "3") (pinfunction "SET_3") (pintype "passive"))
    )
    (net (code "34") (name "unconnected-(U2-ADC6-Pad19)") (class "Default")
      (node (ref "U2") (pin "19") (pinfunction "ADC6_19") (pintype "input+no_connect"))
    )
    (net (code "35") (name "unconnected-(U2-ADC7-Pad22)") (class "Default")
      (node (ref "U2") (pin "22") (pinfunction "ADC7_22") (pintype "input+no_connect"))
    )
    (net (code "36") (name "unconnected-(U2-PB0_(PCINT0{slash}CLKO{slash}ICP1)-Pad12)") (class "Default")
      (node (ref "U2") (pin "12") (pinfunction "PB0_(PCINT0/CLKO/ICP1)_12") (pintype "bidirectional"))
    )
    (net (code "37") (name "unconnected-(U2-PB1_(PCINT1{slash}OC1A)-Pad13)") (class "Default")
      (node (ref "U2") (pin "13") (pinfunction "PB1_(PCINT1/OC1A)_13") (pintype "bidirectional"))
    )
    (net (code "38") (name "unconnected-(U2-PB2_(PCINT2{slash}~{SS}{slash}OC1B)-Pad14)") (class "Default")
      (node (ref "U2") (pin "14") (pinfunction "PB2_(PCINT2/~{SS}/OC1B)_14") (pintype "bidirectional"))
    )
    (net (code "39") (name "unconnected-(U2-PC3_(ADC3{slash}PCINT11)-Pad26)") (class "Default")
      (node (ref "U2") (pin "26") (pinfunction "PC3_(ADC3/PCINT11)_26") (pintype "bidirectional"))
    )
    (net (code "40") (name "unconnected-(U2-PC4_(ADC4{slash}SDA{slash}PCINT12)-Pad27)") (class "Default")
      (node (ref "U2") (pin "27") (pinfunction "PC4_(ADC4/SDA/PCINT12)_27") (pintype "bidirectional"))
    )
    (net (code "41") (name "unconnected-(U2-PC5_(ADC5{slash}SCL{slash}PCINT13)-Pad28)") (class "Default")
      (node (ref "U2") (pin "28") (pinfunction "PC5_(ADC5/SCL/PCINT13)_28") (pintype "bidirectional"))
    )
    (net (code "42") (name "unconnected-(U2-PD2_(INT0{slash}PCINT18)-Pad32)") (class "Default")
      (node (ref "U2") (pin "32") (pinfunction "PD2_(INT0/PCINT18)_32") (pintype "bidirectional"))
    )
    (net (code "43") (name "unconnected-(U2-PD3_(PCINT19{slash}OC2B{slash}INT1)-Pad1)") (class "Default")
      (node (ref "U2") (pin "1") (pinfunction "PD3_(PCINT19/OC2B/INT1)_1") (pintype "bidirectional"))
    )
    (net (code "44") (name "unconnected-(U2-PD4_(PCINT20{slash}XCK{slash}T0)-Pad2)") (class "Default")
      (node (ref "U2") (pin "2") (pinfunction "PD4_(PCINT20/XCK/T0)_2") (pintype "bidirectional"))
    )
    (net (code "45") (name "unconnected-(U2-PD5_(PCINT21{slash}OC0B{slash}T1)-Pad9)") (class "Default")
      (node (ref "U2") (pin "9") (pinfunction "PD5_(PCINT21/OC0B/T1)_9") (pintype "bidirectional"))
    )
    (net (code "46") (name "unconnected-(U2-PD6_(PCINT22{slash}OC0A{slash}AIN0)-Pad10)") (class "Default")
      (node (ref "U2") (pin "10") (pinfunction "PD6_(PCINT22/OC0A/AIN0)_10") (pintype "bidirectional"))
    )
  )
)
